# lm324ecg.net
KiCad netlist of a schematic drawn in EAGLE
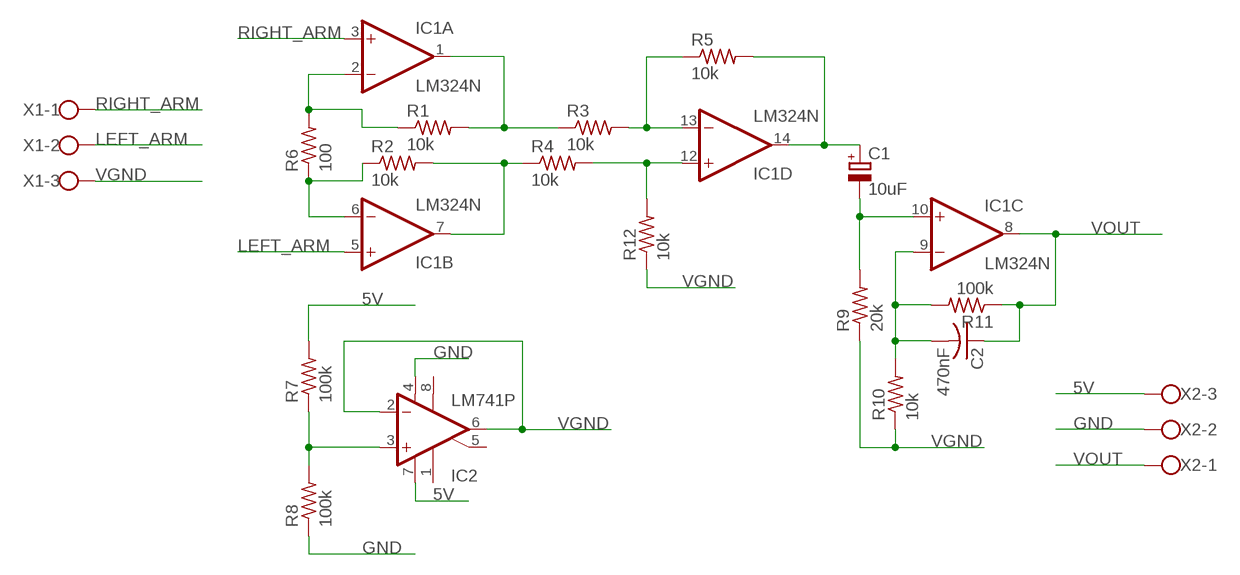
[diagram p0: schematic, sheet 1]

(export (version "E")
  (design (tool "Eeschema 10.0.6"))
  (components
    (comp (ref "C1")
      (value "10uF")
      (footprint "eagle-import:E2,5-7")
      (libsource (lib "eagle-import") (part "CPOL-EUE2.5-7"))
    )
    (comp (ref "C2")
      (value "470nF")
      (footprint "eagle-import:C050-035X075")
      (libsource (lib "eagle-import") (part "C-US050-035X075"))
    )
    (comp (ref "IC1")
      (value "LM324N")
      (footprint "eagle-import:DIL14")
      (libsource (lib "eagle-import") (part "LM324N"))
    )
    (comp (ref "IC2")
      (value "LM741P")
      (footprint "eagle-import:DIL08")
      (libsource (lib "eagle-import") (part "741PLM"))
    )
    (comp (ref "R1")
      (value "10k")
      (footprint "eagle-import:0207_10")
      (libsource (lib "eagle-import") (part "R-US_0207/10"))
    )
    (comp (ref "R2")
      (value "10k")
      (footprint "eagle-import:0207_10")
      (libsource (lib "eagle-import") (part "R-US_0207/10"))
    )
    (comp (ref "R3")
      (value "10k")
      (footprint "eagle-import:0207_10")
      (libsource (lib "eagle-import") (part "R-US_0207/10"))
    )
    (comp (ref "R4")
      (value "10k")
      (footprint "eagle-import:0207_10")
      (libsource (lib "eagle-import") (part "R-US_0207/10"))
    )
    (comp (ref "R5")
      (value "10k")
      (footprint "eagle-import:0207_10")
      (libsource (lib "eagle-import") (part "R-US_0207/10"))
    )
    (comp (ref "R6")
      (value "100")
      (footprint "eagle-import:0207_10")
      (libsource (lib "eagle-import") (part "R-US_0207/10"))
    )
    (comp (ref "R7")
      (value "100k")
      (footprint "eagle-import:0207_10")
      (libsource (lib "eagle-import") (part "R-US_0207/10"))
    )
    (comp (ref "R8")
      (value "100k")
      (footprint "eagle-import:0207_10")
      (libsource (lib "eagle-import") (part "R-US_0207/10"))
    )
    (comp (ref "R9")
      (value "20k")
      (footprint "eagle-import:0207_10")
      (libsource (lib "eagle-import") (part "R-US_0207/10"))
    )
    (comp (ref "R10")
      (value "10k")
      (footprint "eagle-import:0207_10")
      (libsource (lib "eagle-import") (part "R-US_0207/10"))
    )
    (comp (ref "R11")
      (value "100k")
      (footprint "eagle-import:0207_10")
      (libsource (lib "eagle-import") (part "R-US_0207/10"))
    )
    (comp (ref "R12")
      (value "10k")
      (footprint "eagle-import:0207_10")
      (libsource (lib "eagle-import") (part "R-US_0207/10"))
    )
    (comp (ref "X1")
      (value "W237-103")
      (footprint "eagle-import:W237-103")
      (fields (field (name "MPN") "237-103"))
      (libsource (lib "eagle-import") (part "W237-103"))
    )
    (comp (ref "X2")
      (value "W237-103")
      (footprint "eagle-import:W237-103")
      (fields (field (name "MPN") "237-103"))
      (libsource (lib "eagle-import") (part "W237-103"))
    )
  )
  (nets
    (net (code "1") (name "/5V") (class "Default")
      (node (ref "IC2") (pin "7") (pinfunction "V+_7") (pintype "power_in"))
      (node (ref "R7") (pin "2") (pinfunction "2_2") (pintype "passive"))
      (node (ref "X2") (pin "3") (pinfunction "KL_3") (pintype "passive"))
    )
    (net (code "2") (name "/GND") (class "Default")
      (node (ref "IC2") (pin "4") (pinfunction "V-_4") (pintype "power_in"))
      (node (ref "R8") (pin "1") (pinfunction "1_1") (pintype "passive"))
      (node (ref "X2") (pin "2") (pinfunction "KL_2") (pintype "passive"))
    )
    (net (code "3") (name "/LEFT_ARM") (class "Default")
      (node (ref "IC1") (pin "5") (pinfunction "+IN_5") (pintype "input"))
      (node (ref "X1") (pin "2") (pinfunction "KL_2") (pintype "passive"))
    )
    (net (code "4") (name "/RIGHT_ARM") (class "Default")
      (node (ref "IC1") (pin "3") (pinfunction "+IN_3") (pintype "input"))
      (node (ref "X1") (pin "1") (pinfunction "KL_1") (pintype "passive"))
    )
    (net (code "5") (name "/VGND") (class "Default")
      (node (ref "IC2") (pin "2") (pinfunction "-IN_2") (pintype "input"))
      (node (ref "IC2") (pin "6") (pinfunction "OUT_6") (pintype "output"))
      (node (ref "R10") (pin "1") (pinfunction "1_1") (pintype "passive"))
      (node (ref "R12") (pin "1") (pinfunction "1_1") (pintype "passive"))
      (node (ref "R9") (pin "1") (pinfunction "1_1") (pintype "passive"))
      (node (ref "X1") (pin "3") (pinfunction "KL_3") (pintype "passive"))
    )
    (net (code "6") (name "/VOUT") (class "Default")
      (node (ref "C2") (pin "1") (pinfunction "1_1") (pintype "passive"))
      (node (ref "IC1") (pin "8") (pinfunction "OUT_8") (pintype "output"))
      (node (ref "R11") (pin "1") (pinfunction "1_1") (pintype "passive"))
      (node (ref "X2") (pin "1") (pinfunction "KL_1") (pintype "passive"))
    )
    (net (code "7") (name "Net-(IC1A--IN)") (class "Default")
      (node (ref "IC1") (pin "2") (pinfunction "-IN_2") (pintype "input"))
      (node (ref "R1") (pin "1") (pinfunction "1_1") (pintype "passive"))
      (node (ref "R6") (pin "2") (pinfunction "2_2") (pintype "passive"))
    )
    (net (code "8") (name "Net-(IC1A-OUT)") (class "Default")
      (node (ref "IC1") (pin "1") (pinfunction "OUT_1") (pintype "output"))
      (node (ref "R1") (pin "2") (pinfunction "2_2") (pintype "passive"))
      (node (ref "R3") (pin "1") (pinfunction "1_1") (pintype "passive"))
    )
    (net (code "9") (name "Net-(IC1B--IN)") (class "Default")
      (node (ref "IC1") (pin "6") (pinfunction "-IN_6") (pintype "input"))
      (node (ref "R2") (pin "1") (pinfunction "1_1") (pintype "passive"))
      (node (ref "R6") (pin "1") (pinfunction "1_1") (pintype "passive"))
    )
    (net (code "10") (name "Net-(IC1B-OUT)") (class "Default")
      (node (ref "IC1") (pin "7") (pinfunction "OUT_7") (pintype "output"))
      (node (ref "R2") (pin "2") (pinfunction "2_2") (pintype "passive"))
      (node (ref "R4") (pin "1") (pinfunction "1_1") (pintype "passive"))
    )
    (net (code "11") (name "Net-(IC1C-+IN)") (class "Default")
      (node (ref "C1") (pin "-") (pinfunction "-_-") (pintype "passive"))
      (node (ref "IC1") (pin "10") (pinfunction "+IN_10") (pintype "input"))
      (node (ref "R9") (pin "2") (pinfunction "2_2") (pintype "passive"))
    )
    (net (code "12") (name "Net-(IC1C--IN)") (class "Default")
      (node (ref "C2") (pin "2") (pinfunction "2_2") (pintype "passive"))
      (node (ref "IC1") (pin "9") (pinfunction "-IN_9") (pintype "input"))
      (node (ref "R10") (pin "2") (pinfunction "2_2") (pintype "passive"))
      (node (ref "R11") (pin "2") (pinfunction "2_2") (pintype "passive"))
    )
    (net (code "13") (name "Net-(IC1D-+IN)") (class "Default")
      (node (ref "IC1") (pin "12") (pinfunction "+IN_12") (pintype "input"))
      (node (ref "R12") (pin "2") (pinfunction "2_2") (pintype "passive"))
      (node (ref "R4") (pin "2") (pinfunction "2_2") (pintype "passive"))
    )
    (net (code "14") (name "Net-(IC1D--IN)") (class "Default")
      (node (ref "IC1") (pin "13") (pinfunction "-IN_13") (pintype "input"))
      (node (ref "R3") (pin "2") (pinfunction "2_2") (pintype "passive"))
      (node (ref "R5") (pin "1") (pinfunction "1_1") (pintype "passive"))
    )
    (net (code "15") (name "Net-(IC1D-OUT)") (class "Default")
      (node (ref "C1") (pin "+") (pinfunction "+_+") (pintype "passive"))
      (node (ref "IC1") (pin "14") (pinfunction "OUT_14") (pintype "output"))
      (node (ref "R5") (pin "2") (pinfunction "2_2") (pintype "passive"))
    )
    (net (code "16") (name "Net-(IC2-+IN)") (class "Default")
      (node (ref "IC2") (pin "3") (pinfunction "+IN_3") (pintype "input"))
      (node (ref "R7") (pin "1") (pinfunction "1_1") (pintype "passive"))
      (node (ref "R8") (pin "2") (pinfunction "2_2") (pintype "passive"))
    )
    (net (code "17") (name "unconnected-(IC2-ON1-Pad1)") (class "Default")
      (node (ref "IC2") (pin "1") (pinfunction "ON1_1") (pintype "passive"))
    )
    (net (code "18") (name "unconnected-(IC2-ON2-Pad5)") (class "Default")
      (node (ref "IC2") (pin "5") (pinfunction "ON2_5") (pintype "passive"))
    )
    (net (code "19") (name "unconnected-(IC2-OPT-Pad8)") (class "Default")
      (node (ref "IC2") (pin "8") (pinfunction "OPT_8") (pintype "passive"))
    )
  )
)
